# v20.net
KiCad netlist of a schematic drawn in EAGLE
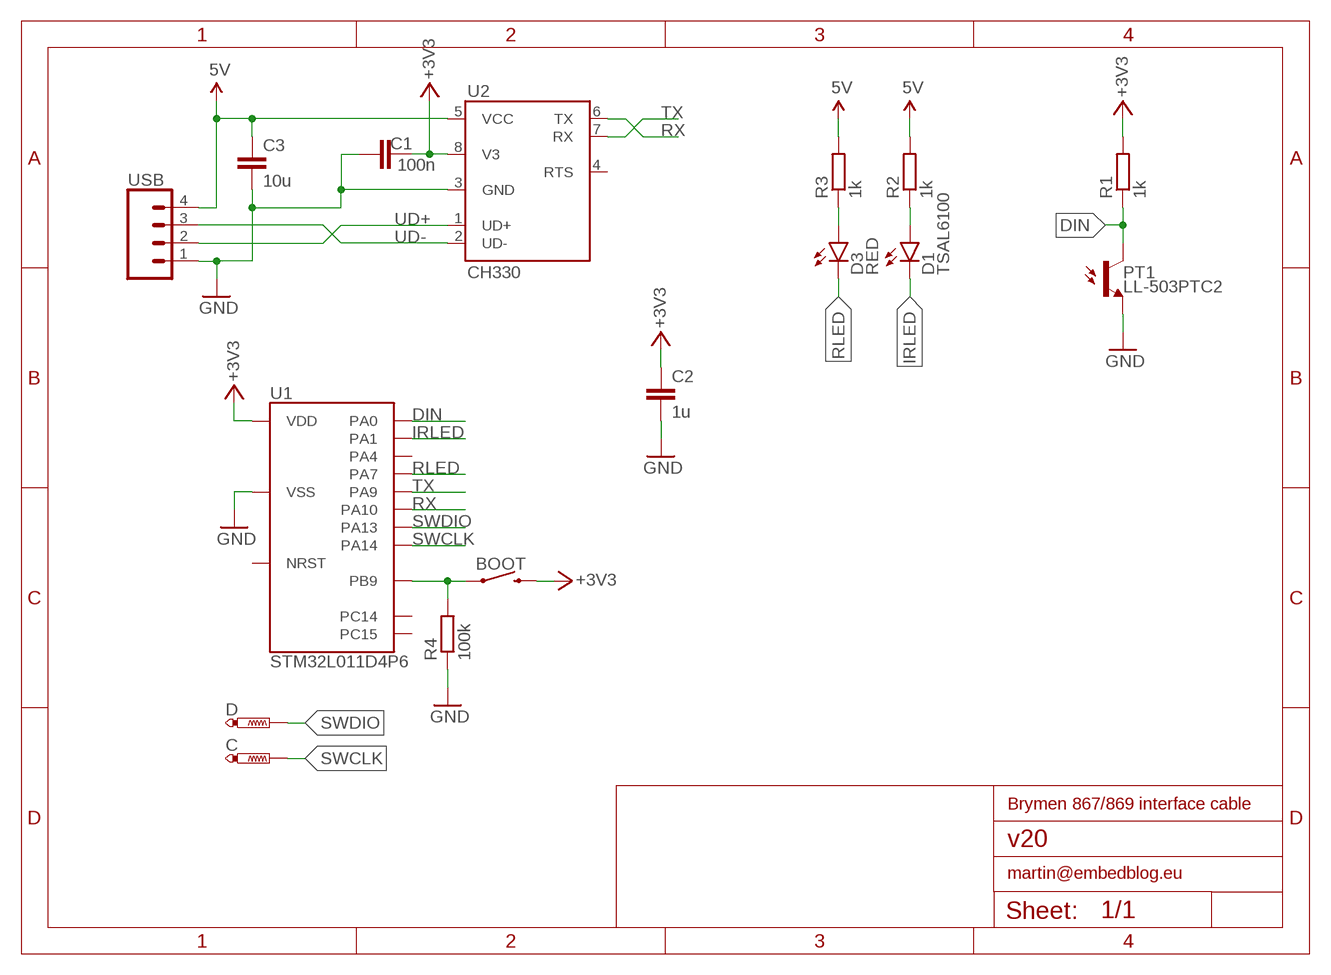
[diagram p0: schematic, sheet 1]

(export (version "E")
  (design (tool "Eeschema 10.0.6"))
  (components
    (comp (ref "BOOT")
      (value "MOMENTARY-SWITCH-SPST-SMD-5.2MM")
      (footprint "eagle-import:TACTILE_SWITCH_SMD_5.2MM")
      (libsource (lib "eagle-import") (part "MOMENTARY-SWITCH-SPST-SMD-5.2MM"))
    )
    (comp (ref "C")
      (value "PTR1B1,27")
      (footprint "eagle-import:B1,27")
      (libsource (lib "eagle-import") (part "PTR1B1,27"))
    )
    (comp (ref "C1")
      (value "100n")
      (footprint "eagle-import:C0805")
      (libsource (lib "eagle-import") (part "C-EUC0805"))
    )
    (comp (ref "C2")
      (value "1u")
      (footprint "eagle-import:C0805")
      (libsource (lib "eagle-import") (part "C-EUC0805"))
    )
    (comp (ref "C3")
      (value "10u")
      (footprint "eagle-import:C0805")
      (libsource (lib "eagle-import") (part "C-EUC0805"))
    )
    (comp (ref "D")
      (value "PTR1B1,27")
      (footprint "eagle-import:B1,27")
      (libsource (lib "eagle-import") (part "PTR1B1,27"))
    )
    (comp (ref "D1")
      (value "TSAL6100")
      (footprint "eagle-import:LED5MM")
      (libsource (lib "eagle-import") (part "LED5MM"))
    )
    (comp (ref "D3")
      (value "RED")
      (footprint "eagle-import:LED-1206")
      (libsource (lib "eagle-import") (part "LED1206"))
    )
    (comp (ref "PT1")
      (value "LL-503PTC2")
      (footprint "eagle-import:LED5MM")
      (libsource (lib "eagle-import") (part "LL-503_PHOTOTRANSISTOR"))
    )
    (comp (ref "R1")
      (value "1k")
      (footprint "eagle-import:R0805")
      (libsource (lib "eagle-import") (part "R-EU_R0805"))
    )
    (comp (ref "R2")
      (value "1k")
      (footprint "eagle-import:R0805")
      (libsource (lib "eagle-import") (part "R-EU_R0805"))
    )
    (comp (ref "R3")
      (value "1k")
      (footprint "eagle-import:R0805")
      (libsource (lib "eagle-import") (part "R-EU_R0805"))
    )
    (comp (ref "R4")
      (value "100k")
      (footprint "eagle-import:R0805")
      (libsource (lib "eagle-import") (part "R-EU_R0805"))
    )
    (comp (ref "U1")
      (value "STM32L011D4P6")
      (footprint "eagle-import:TSSOP14")
      (libsource (lib "eagle-import") (part "STM32L011D4P6"))
    )
    (comp (ref "U2")
      (value "CH330")
      (footprint "eagle-import:SO08")
      (libsource (lib "eagle-import") (part "CH330"))
    )
    (comp (ref "USB")
      (value "CONN_04")
      (footprint "eagle-import:1X04")
      (libsource (lib "eagle-import") (part "CONN_04"))
    )
  )
  (nets
    (net (code "1") (name "+3V3") (class "Default")
      (node (ref "BOOT") (pin "3") (pinfunction "2_3") (pintype "passive"))
      (node (ref "C1") (pin "2") (pinfunction "2_2") (pintype "passive"))
      (node (ref "C2") (pin "1") (pinfunction "1_1") (pintype "passive"))
      (node (ref "R1") (pin "2") (pinfunction "2_2") (pintype "passive"))
      (node (ref "U1") (pin "10") (pinfunction "VDD_10") (pintype "power_in"))
      (node (ref "U2") (pin "8") (pinfunction "V3_8") (pintype "bidirectional"))
    )
    (net (code "2") (name "/RX") (class "Default")
      (node (ref "U1") (pin "12") (pinfunction "PA10_12") (pintype "bidirectional"))
      (node (ref "U2") (pin "6") (pinfunction "TX_6") (pintype "bidirectional"))
    )
    (net (code "3") (name "/TX") (class "Default")
      (node (ref "U1") (pin "11") (pinfunction "PA9_11") (pintype "bidirectional"))
      (node (ref "U2") (pin "7") (pinfunction "RX_7") (pintype "bidirectional"))
    )
    (net (code "4") (name "/UD+") (class "Default")
      (node (ref "U2") (pin "1") (pinfunction "UD+_1") (pintype "bidirectional"))
      (node (ref "USB") (pin "2") (pinfunction "2_2") (pintype "passive"))
    )
    (net (code "5") (name "/UD-") (class "Default")
      (node (ref "U2") (pin "2") (pinfunction "UD-_2") (pintype "bidirectional"))
      (node (ref "USB") (pin "3") (pinfunction "3_3") (pintype "passive"))
    )
    (net (code "6") (name "5V") (class "Default")
      (node (ref "C3") (pin "1") (pinfunction "1_1") (pintype "passive"))
      (node (ref "R2") (pin "2") (pinfunction "2_2") (pintype "passive"))
      (node (ref "R3") (pin "2") (pinfunction "2_2") (pintype "passive"))
      (node (ref "U2") (pin "5") (pinfunction "VCC_5") (pintype "bidirectional"))
      (node (ref "USB") (pin "4") (pinfunction "4_4") (pintype "passive"))
    )
    (net (code "7") (name "DIN") (class "Default")
      (node (ref "PT1") (pin "K") (pinfunction "C_K") (pintype "passive"))
      (node (ref "R1") (pin "1") (pinfunction "1_1") (pintype "passive"))
      (node (ref "U1") (pin "5") (pinfunction "PA0_5") (pintype "bidirectional"))
    )
    (net (code "8") (name "GND") (class "Default")
      (node (ref "C1") (pin "1") (pinfunction "1_1") (pintype "passive"))
      (node (ref "C2") (pin "2") (pinfunction "2_2") (pintype "passive"))
      (node (ref "C3") (pin "2") (pinfunction "2_2") (pintype "passive"))
      (node (ref "PT1") (pin "A") (pinfunction "E_A") (pintype "passive"))
      (node (ref "R4") (pin "1") (pinfunction "1_1") (pintype "passive"))
      (node (ref "U1") (pin "9") (pinfunction "VSS_9") (pintype "power_in"))
      (node (ref "U2") (pin "3") (pinfunction "GND_3") (pintype "bidirectional"))
      (node (ref "USB") (pin "1") (pinfunction "1_1") (pintype "passive"))
    )
    (net (code "9") (name "IRLED") (class "Default")
      (node (ref "D1") (pin "K") (pinfunction "C_K") (pintype "passive"))
      (node (ref "U1") (pin "6") (pinfunction "PA1_6") (pintype "bidirectional"))
    )
    (net (code "10") (name "Net-(D1-PadA)") (class "Default")
      (node (ref "D1") (pin "A") (pinfunction "A_A") (pintype "passive"))
      (node (ref "R2") (pin "1") (pinfunction "1_1") (pintype "passive"))
    )
    (net (code "11") (name "Net-(D3-PadA)") (class "Default")
      (node (ref "D3") (pin "A") (pinfunction "A_A") (pintype "passive"))
      (node (ref "R3") (pin "1") (pinfunction "1_1") (pintype "passive"))
    )
    (net (code "12") (name "Net-(U1-PB9)") (class "Default")
      (node (ref "BOOT") (pin "1") (pinfunction "1_1") (pintype "passive"))
      (node (ref "R4") (pin "2") (pinfunction "2_2") (pintype "passive"))
      (node (ref "U1") (pin "1") (pinfunction "PB9_1") (pintype "bidirectional"))
    )
    (net (code "13") (name "RLED") (class "Default")
      (node (ref "D3") (pin "C") (pinfunction "C_C") (pintype "passive"))
      (node (ref "U1") (pin "8") (pinfunction "PA7_8") (pintype "bidirectional"))
    )
    (net (code "14") (name "SWCLK") (class "Default")
      (node (ref "C") (pin "TP") (pinfunction "TP_TP") (pintype "input"))
      (node (ref "U1") (pin "14") (pinfunction "PA14_14") (pintype "bidirectional"))
    )
    (net (code "15") (name "SWDIO") (class "Default")
      (node (ref "D") (pin "TP") (pinfunction "TP_TP") (pintype "input"))
      (node (ref "U1") (pin "13") (pinfunction "PA13_13") (pintype "bidirectional"))
    )
    (net (code "16") (name "unconnected-(U1-NRST-Pad4)") (class "Default")
      (node (ref "U1") (pin "4") (pinfunction "NRST_4") (pintype "input"))
    )
    (net (code "17") (name "unconnected-(U1-PA4-Pad7)") (class "Default")
      (node (ref "U1") (pin "7") (pinfunction "PA4_7") (pintype "bidirectional"))
    )
    (net (code "18") (name "unconnected-(U1-PC14-Pad2)") (class "Default")
      (node (ref "U1") (pin "2") (pinfunction "PC14_2") (pintype "bidirectional"))
    )
    (net (code "19") (name "unconnected-(U1-PC15-Pad3)") (class "Default")
      (node (ref "U1") (pin "3") (pinfunction "PC15_3") (pintype "bidirectional"))
    )
    (net (code "20") (name "unconnected-(U2-RTS-Pad4)") (class "Default")
      (node (ref "U2") (pin "4") (pinfunction "RTS_4") (pintype "bidirectional"))
    )
  )
)
